# rapidshark-flywheel-controller-mk-1_2.net
KiCad netlist of a schematic drawn in EAGLE
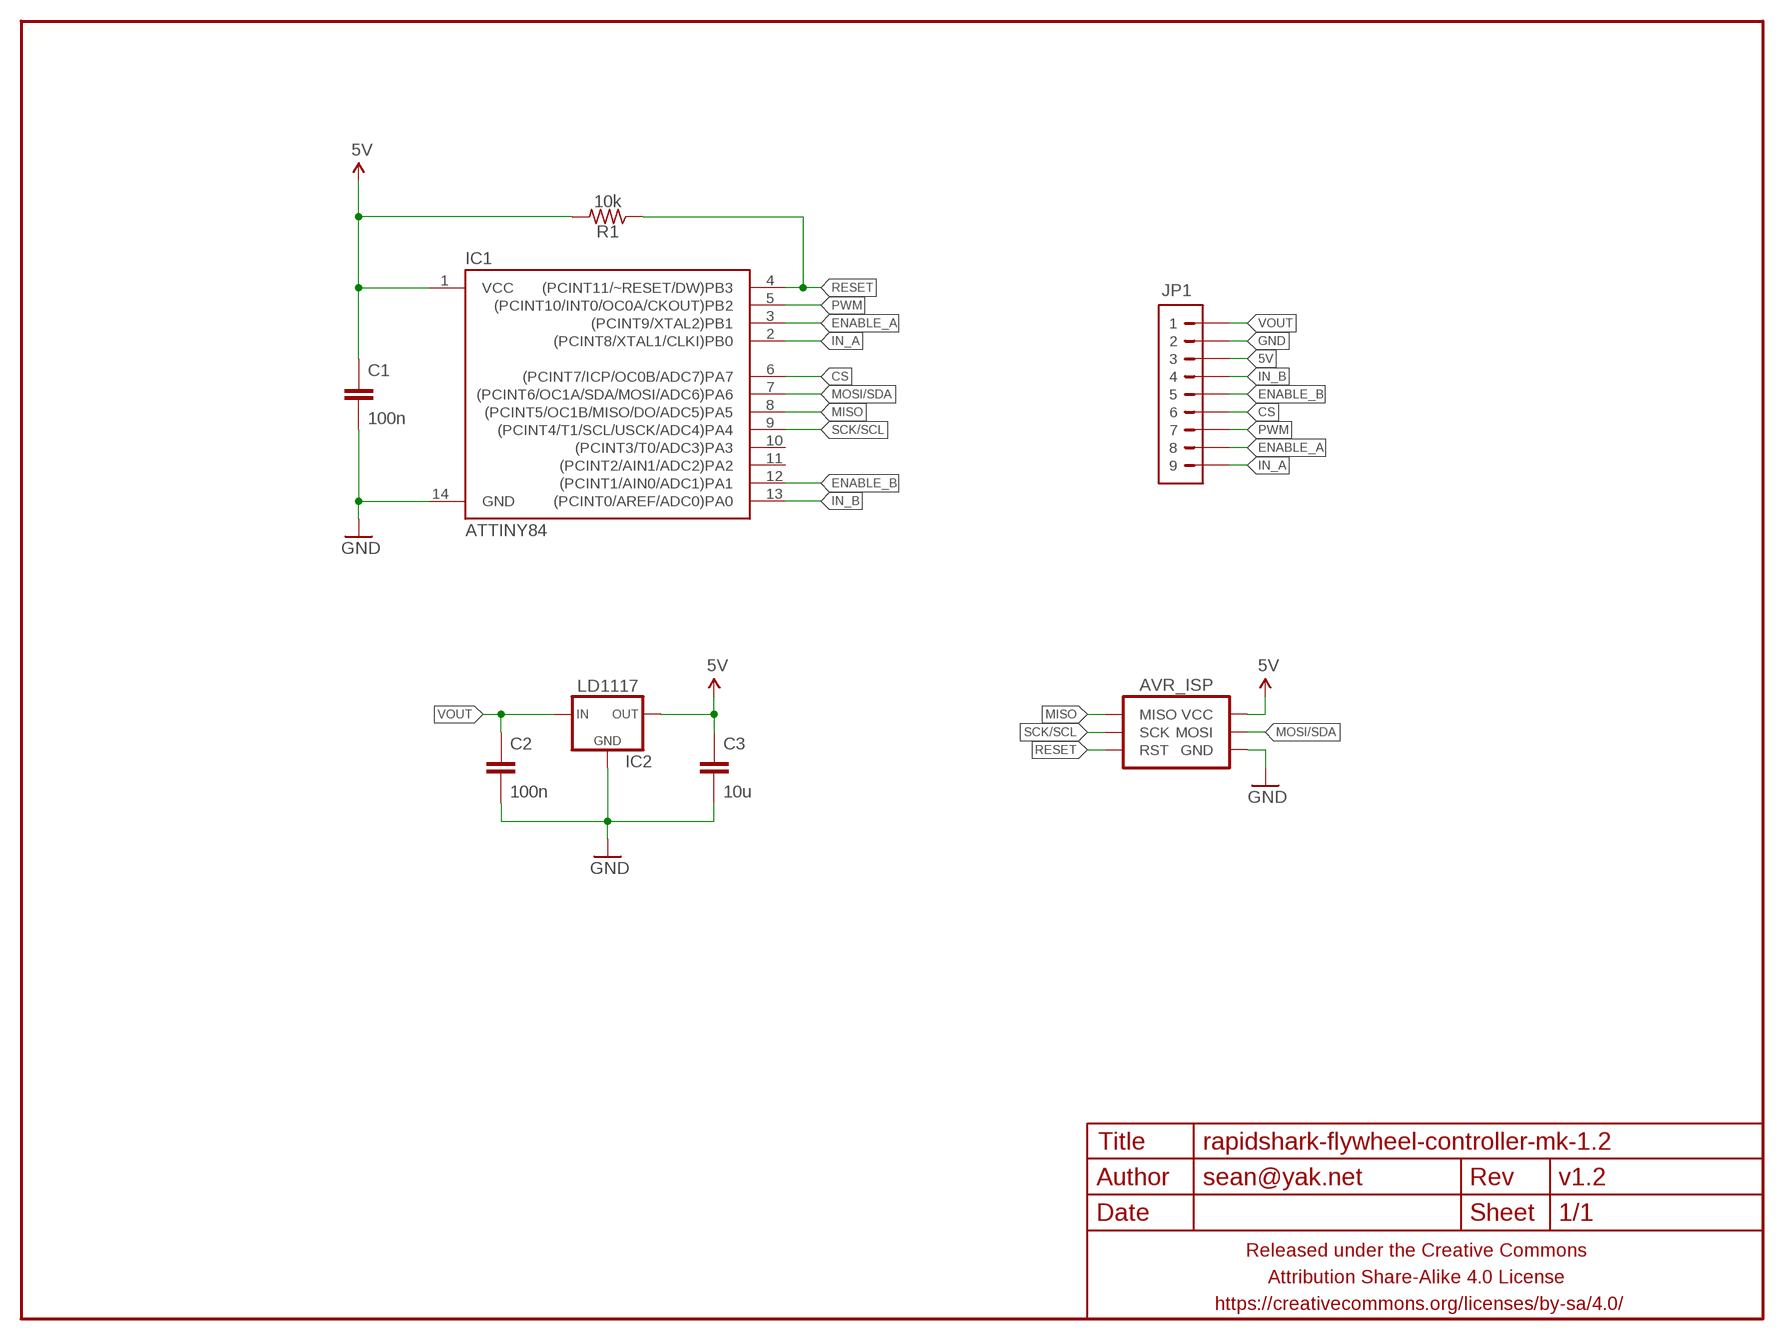
[diagram p0: schematic, sheet 1]

(export (version "E")
  (design (tool "Eeschema 10.0.6"))
  (components
    (comp (ref "AVR_ISP")
      (value "AVR_SPI_PRG_6JST-PH-VERT-PTH1")
      (footprint "eagle-import:JST-6-PH-VERT-PTH")
      (libsource (lib "eagle-import") (part "AVR_SPI_PRG_6JST-PH-VERT-PTH1"))
    )
    (comp (ref "C1")
      (value "100n")
      (footprint "eagle-import:C0805")
      (libsource (lib "eagle-import") (part "CAPACITOR-CERAMICC0805"))
    )
    (comp (ref "C2")
      (value "100n")
      (footprint "eagle-import:C0805")
      (libsource (lib "eagle-import") (part "CAPACITOR-CERAMICC0805"))
    )
    (comp (ref "C3")
      (value "10u")
      (footprint "eagle-import:C1206")
      (libsource (lib "eagle-import") (part "CAPACITOR-CERAMICC1206"))
    )
    (comp (ref "FRAME1")
      (value "FRAME-LETTERNO_PACKAGE")
      (footprint "eagle-import:DUMMY")
      (fields (field (name "DESIGNER") "sean@yak.net") (field (name "VERSION") "v1.2"))
      (libsource (lib "eagle-import") (part "FRAME-LETTERNO_PACKAGE"))
    )
    (comp (ref "IC1")
      (value "ATTINY84")
      (footprint "eagle-import:SO14")
      (libsource (lib "eagle-import") (part "ATTINY84"))
    )
    (comp (ref "IC2")
      (value "LD1117")
      (footprint "eagle-import:SOT223")
      (libsource (lib "eagle-import") (part "V_REG_78XXSOT-223"))
    )
    (comp (ref "JP1")
      (value "M09CENTERED")
      (footprint "eagle-import:1X09-CENTERED")
      (libsource (lib "eagle-import") (part "M09CENTERED"))
    )
    (comp (ref "R1")
      (value "10k")
      (footprint "eagle-import:R0805")
      (libsource (lib "eagle-import") (part "RESISTORR0805"))
    )
  )
  (nets
    (net (code "1") (name "5V") (class "Default")
      (node (ref "AVR_ISP") (pin "1") (pinfunction "VCC_1") (pintype "passive"))
      (node (ref "C1") (pin "1") (pinfunction "1_1") (pintype "passive"))
      (node (ref "C3") (pin "1") (pinfunction "1_1") (pintype "passive"))
      (node (ref "IC1") (pin "1") (pinfunction "VCC_1") (pintype "bidirectional"))
      (node (ref "IC2") (pin "2") (pinfunction "OUT_2") (pintype "bidirectional"))
      (node (ref "IC2") (pin "4") (pinfunction "OUT_4") (pintype "bidirectional"))
      (node (ref "JP1") (pin "3") (pinfunction "3_3") (pintype "bidirectional"))
      (node (ref "R1") (pin "2") (pinfunction "2_2") (pintype "passive"))
    )
    (net (code "2") (name "CS") (class "Default")
      (node (ref "IC1") (pin "6") (pinfunction "(PCINT7/ICP/OC0B/ADC7)PA7_6") (pintype "bidirectional"))
      (node (ref "JP1") (pin "6") (pinfunction "6_6") (pintype "bidirectional"))
    )
    (net (code "3") (name "ENABLE_A") (class "Default")
      (node (ref "IC1") (pin "3") (pinfunction "(PCINT9/XTAL2)PB1_3") (pintype "bidirectional"))
      (node (ref "JP1") (pin "8") (pinfunction "8_8") (pintype "bidirectional"))
    )
    (net (code "4") (name "ENABLE_B") (class "Default")
      (node (ref "IC1") (pin "12") (pinfunction "(PCINT1/AIN0/ADC1)PA1_12") (pintype "bidirectional"))
      (node (ref "JP1") (pin "5") (pinfunction "5_5") (pintype "bidirectional"))
    )
    (net (code "5") (name "GND") (class "Default")
      (node (ref "AVR_ISP") (pin "6") (pinfunction "GND_6") (pintype "passive"))
      (node (ref "C1") (pin "2") (pinfunction "2_2") (pintype "passive"))
      (node (ref "C2") (pin "2") (pinfunction "2_2") (pintype "passive"))
      (node (ref "C3") (pin "2") (pinfunction "2_2") (pintype "passive"))
      (node (ref "IC1") (pin "14") (pinfunction "GND_14") (pintype "bidirectional"))
      (node (ref "IC2") (pin "1") (pinfunction "GND_1") (pintype "bidirectional"))
      (node (ref "JP1") (pin "2") (pinfunction "2_2") (pintype "bidirectional"))
    )
    (net (code "6") (name "IN_A") (class "Default")
      (node (ref "IC1") (pin "2") (pinfunction "(PCINT8/XTAL1/CLKI)PB0_2") (pintype "bidirectional"))
      (node (ref "JP1") (pin "9") (pinfunction "9_9") (pintype "bidirectional"))
    )
    (net (code "7") (name "IN_B") (class "Default")
      (node (ref "IC1") (pin "13") (pinfunction "(PCINT0/AREF/ADC0)PA0_13") (pintype "bidirectional"))
      (node (ref "JP1") (pin "4") (pinfunction "4_4") (pintype "bidirectional"))
    )
    (net (code "8") (name "MISO") (class "Default")
      (node (ref "AVR_ISP") (pin "2") (pinfunction "MISO_2") (pintype "passive"))
      (node (ref "IC1") (pin "8") (pinfunction "(PCINT5/OC1B/MISO/DO/ADC5)PA5_8") (pintype "bidirectional"))
    )
    (net (code "9") (name "MOSI{slash}SDA") (class "Default")
      (node (ref "AVR_ISP") (pin "4") (pinfunction "MOSI_4") (pintype "passive"))
      (node (ref "IC1") (pin "7") (pinfunction "(PCINT6/OC1A/SDA/MOSI/ADC6)PA6_7") (pintype "bidirectional"))
    )
    (net (code "10") (name "PWM") (class "Default")
      (node (ref "IC1") (pin "5") (pinfunction "(PCINT10/INT0/OC0A/CKOUT)PB2_5") (pintype "bidirectional"))
      (node (ref "JP1") (pin "7") (pinfunction "7_7") (pintype "bidirectional"))
    )
    (net (code "11") (name "RESET") (class "Default")
      (node (ref "AVR_ISP") (pin "5") (pinfunction "RST_5") (pintype "passive"))
      (node (ref "IC1") (pin "4") (pinfunction "(PCINT11/~{RESET/DW})PB3_4") (pintype "bidirectional"))
      (node (ref "R1") (pin "1") (pinfunction "1_1") (pintype "passive"))
    )
    (net (code "12") (name "SCK{slash}SCL") (class "Default")
      (node (ref "AVR_ISP") (pin "3") (pinfunction "SCK_3") (pintype "passive"))
      (node (ref "IC1") (pin "9") (pinfunction "(PCINT4/T1/SCL/USCK/ADC4)PA4_9") (pintype "bidirectional"))
    )
    (net (code "13") (name "VOUT") (class "Default")
      (node (ref "C2") (pin "1") (pinfunction "1_1") (pintype "passive"))
      (node (ref "IC2") (pin "3") (pinfunction "IN_3") (pintype "bidirectional"))
      (node (ref "JP1") (pin "1") (pinfunction "1_1") (pintype "bidirectional"))
    )
    (net (code "14") (name "unconnected-(IC1-(PCINT2{slash}AIN1{slash}ADC2)PA2-Pad11)") (class "Default")
      (node (ref "IC1") (pin "11") (pinfunction "(PCINT2/AIN1/ADC2)PA2_11") (pintype "bidirectional"))
    )
    (net (code "15") (name "unconnected-(IC1-(PCINT3{slash}T0{slash}ADC3)PA3-Pad10)") (class "Default")
      (node (ref "IC1") (pin "10") (pinfunction "(PCINT3/T0/ADC3)PA3_10") (pintype "bidirectional"))
    )
  )
)
